# DRV8874_MOTOR_DRV.net
KiCad netlist of a schematic drawn in Altium Designer
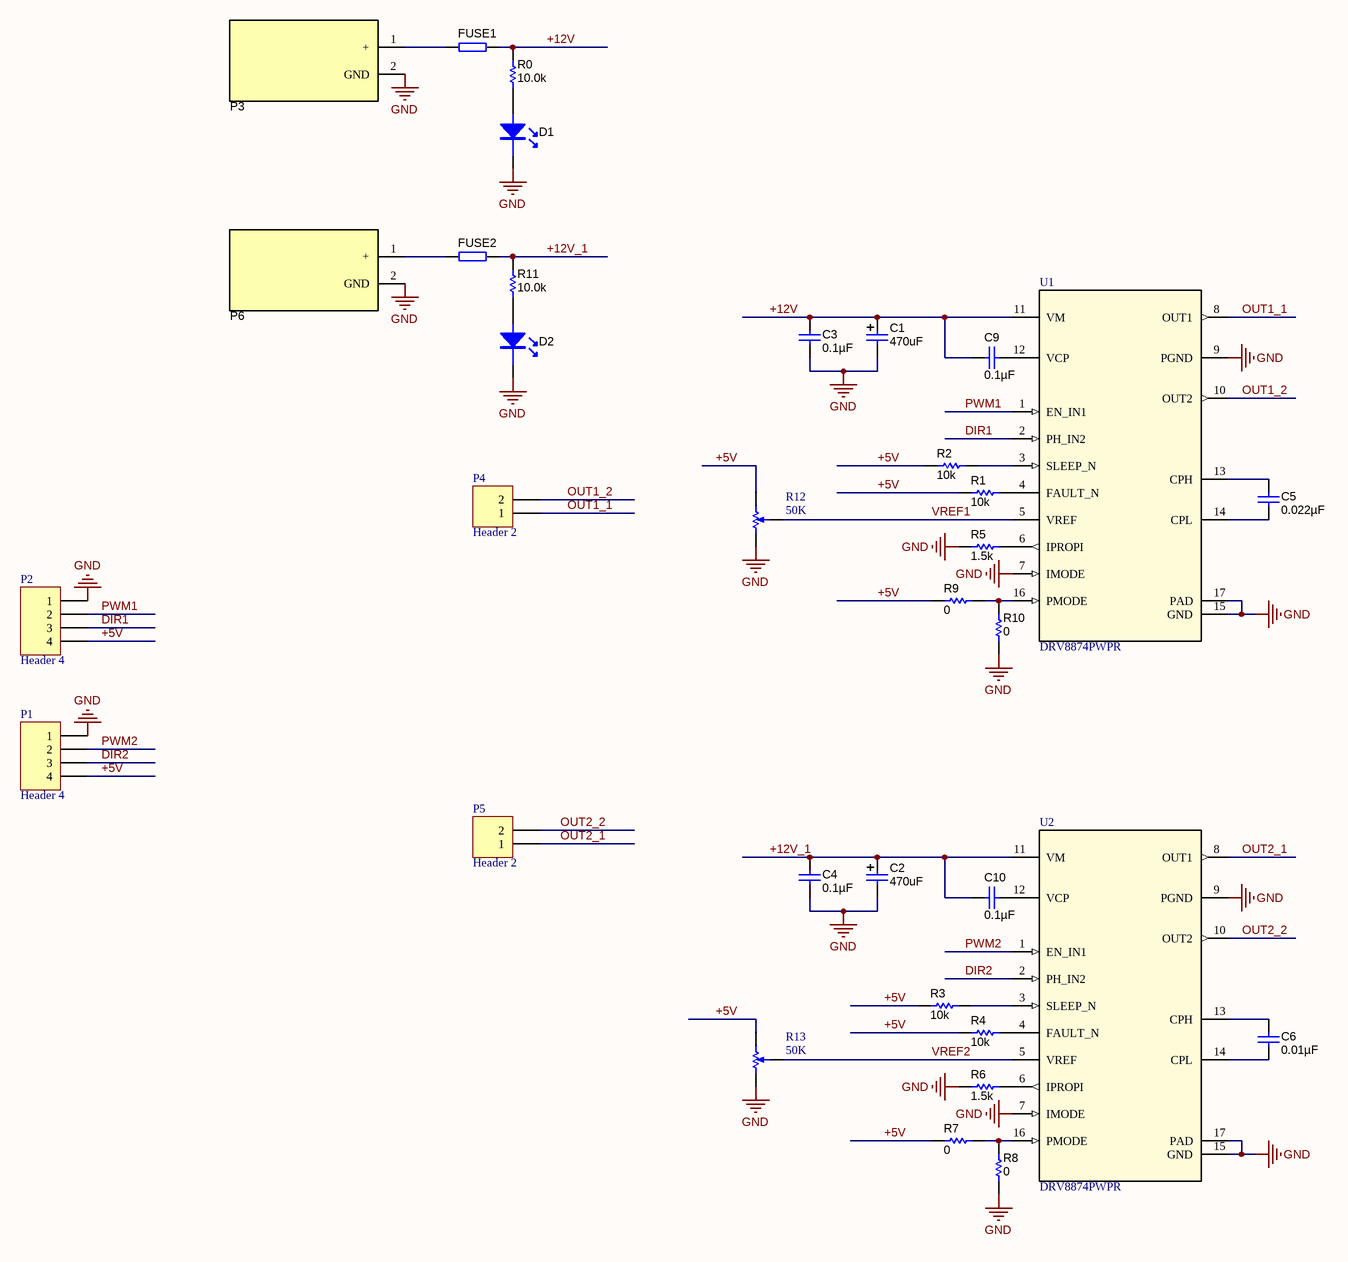
[diagram p0: DRV8874 MOTOR DRV.SchDoc]

(export (version "E")
  (design (tool "Eeschema 10.0.6"))
  (components
    (comp (ref "C1")
      (value "470uF")
      (footprint "CAP")
      (fields (field (name "MANUFACTURER") "Used in BOM report"))
      (libsource (lib "LMD18200 MOTOR DRV") (part "Cap_100uF"))
    )
    (comp (ref "C2")
      (value "470uF")
      (footprint "CAP")
      (fields (field (name "MANUFACTURER") "Used in BOM report"))
      (libsource (lib "LMD18200 MOTOR DRV") (part "Cap_100uF"))
    )
    (comp (ref "C3")
      (value "08051C103JAT2A")
      (footprint "0805_HV")
      (description "CAP, CERM, 0.01 µF, 100 V, +/- 5%, X7R, 0805")
      (fields
        (field (name "VALUEDISPLAYED") "0.1µF")
        (field (name "MANUFACTURER") "AVX")
        (field (name "PUBLISHER") "Texas Instruments")
      )
      (libsource (lib "VFD_CLOCK") (part "08051C103JAT2A"))
    )
    (comp (ref "C4")
      (value "08051C103JAT2A")
      (footprint "0805_HV")
      (description "CAP, CERM, 0.01 µF, 100 V, +/- 5%, X7R, 0805")
      (fields
        (field (name "VALUEDISPLAYED") "0.1µF")
        (field (name "MANUFACTURER") "AVX")
        (field (name "PUBLISHER") "Texas Instruments")
      )
      (libsource (lib "VFD_CLOCK") (part "08051C103JAT2A"))
    )
    (comp (ref "C5")
      (value "08051C103JAT2A")
      (footprint "0805_HV")
      (description "CAP, CERM, 0.01 µF, 100 V, +/- 5%, X7R, 0805")
      (fields
        (field (name "VALUEDISPLAYED") "0.022µF")
        (field (name "MANUFACTURER") "AVX")
        (field (name "PUBLISHER") "Texas Instruments")
      )
      (libsource (lib "VFD_CLOCK") (part "08051C103JAT2A"))
    )
    (comp (ref "C6")
      (value "08051C103JAT2A")
      (footprint "0805_HV")
      (description "CAP, CERM, 0.01 µF, 100 V, +/- 5%, X7R, 0805")
      (fields
        (field (name "VALUEDISPLAYED") "0.01µF")
        (field (name "MANUFACTURER") "AVX")
        (field (name "PUBLISHER") "Texas Instruments")
      )
      (libsource (lib "VFD_CLOCK") (part "08051C103JAT2A"))
    )
    (comp (ref "C9")
      (value "08051C103JAT2A")
      (footprint "0805_HV")
      (description "CAP, CERM, 0.01 µF, 100 V, +/- 5%, X7R, 0805")
      (fields
        (field (name "VALUEDISPLAYED") "0.1µF")
        (field (name "MANUFACTURER") "AVX")
        (field (name "PUBLISHER") "Texas Instruments")
      )
      (libsource (lib "VFD_CLOCK") (part "08051C103JAT2A"))
    )
    (comp (ref "C10")
      (value "08051C103JAT2A")
      (footprint "0805_HV")
      (description "CAP, CERM, 0.01 µF, 100 V, +/- 5%, X7R, 0805")
      (fields
        (field (name "VALUEDISPLAYED") "0.1µF")
        (field (name "MANUFACTURER") "AVX")
        (field (name "PUBLISHER") "Texas Instruments")
      )
      (libsource (lib "VFD_CLOCK") (part "08051C103JAT2A"))
    )
    (comp (ref "D1")
      (value "RED")
      (footprint "0805_HV")
      (description "LED发光管")
      (libsource (lib "Buffer_Board") (part "LED"))
    )
    (comp (ref "D2")
      (value "RED")
      (footprint "0805_HV")
      (description "LED发光管")
      (libsource (lib "Buffer_Board") (part "LED"))
    )
    (comp (ref "FUSE1")
      (value "~")
      (footprint "1206")
      (description "电阻")
      (libsource (lib "Buffer_Board") (part "R"))
    )
    (comp (ref "FUSE2")
      (value "~")
      (footprint "1206")
      (description "电阻")
      (libsource (lib "Buffer_Board") (part "R"))
    )
    (comp (ref "P1")
      (value "Header 4")
      (footprint "HDR1X4")
      (description "Header, 4-Pin")
      (fields (field (name "PUBLISHER") "Altium Limited"))
      (libsource (lib "Miscellaneous Connectors") (part "Header 4"))
    )
    (comp (ref "P2")
      (value "Header 4")
      (footprint "HDR1X4")
      (description "Header, 4-Pin")
      (fields (field (name "PUBLISHER") "Altium Limited"))
      (libsource (lib "Miscellaneous Connectors") (part "Header 4"))
    )
    (comp (ref "P3")
      (value "Used in BOM report")
      (footprint "2p")
      (libsource (lib "VFD_CLOCK") (part "PWR5.5"))
    )
    (comp (ref "P4")
      (value "Header 2")
      (footprint "2p")
      (description "Header, 2-Pin")
      (fields (field (name "PUBLISHER") "Altium Limited"))
      (libsource (lib "Miscellaneous Connectors") (part "Header 2"))
    )
    (comp (ref "P5")
      (value "Header 2")
      (footprint "2p")
      (description "Header, 2-Pin")
      (fields (field (name "PUBLISHER") "Altium Limited"))
      (libsource (lib "Miscellaneous Connectors") (part "Header 2"))
    )
    (comp (ref "P6")
      (value "Used in BOM report")
      (footprint "2p")
      (libsource (lib "VFD_CLOCK") (part "PWR5.5"))
    )
    (comp (ref "R0")
      (value "CRCW080510K0FKEA")
      (footprint "0805_HV")
      (description "RES, 10.0 k, 1%, 0.125 W, 0805")
      (fields
        (field (name "MANUFACTURER") "Vishay-Dale")
        (field (name "VALUEDISPLAYED") "10.0k")
        (field (name "PUBLISHER") "Texas Instruments")
      )
      (libsource (lib "VFD_CLOCK") (part "CRCW080510K0FKEA"))
    )
    (comp (ref "R1")
      (value "CRCW080510K0FKEA")
      (footprint "0805_HV")
      (description "RES, 10.0 k, 1%, 0.125 W, 0805")
      (fields
        (field (name "MANUFACTURER") "Vishay-Dale")
        (field (name "VALUEDISPLAYED") "10k")
        (field (name "PUBLISHER") "Texas Instruments")
      )
      (libsource (lib "VFD_CLOCK") (part "CRCW080510K0FKEA"))
    )
    (comp (ref "R2")
      (value "CRCW080510K0FKEA")
      (footprint "0805_HV")
      (description "RES, 10.0 k, 1%, 0.125 W, 0805")
      (fields
        (field (name "MANUFACTURER") "Vishay-Dale")
        (field (name "VALUEDISPLAYED") "10k")
        (field (name "PUBLISHER") "Texas Instruments")
      )
      (libsource (lib "VFD_CLOCK") (part "CRCW080510K0FKEA"))
    )
    (comp (ref "R3")
      (value "CRCW080510K0FKEA")
      (footprint "0805_HV")
      (description "RES, 10.0 k, 1%, 0.125 W, 0805")
      (fields
        (field (name "MANUFACTURER") "Vishay-Dale")
        (field (name "VALUEDISPLAYED") "10k")
        (field (name "PUBLISHER") "Texas Instruments")
      )
      (libsource (lib "VFD_CLOCK") (part "CRCW080510K0FKEA"))
    )
    (comp (ref "R4")
      (value "CRCW080510K0FKEA")
      (footprint "0805_HV")
      (description "RES, 10.0 k, 1%, 0.125 W, 0805")
      (fields
        (field (name "MANUFACTURER") "Vishay-Dale")
        (field (name "VALUEDISPLAYED") "10k")
        (field (name "PUBLISHER") "Texas Instruments")
      )
      (libsource (lib "VFD_CLOCK") (part "CRCW080510K0FKEA"))
    )
    (comp (ref "R5")
      (value "CRCW080510K0FKEA")
      (footprint "0805_HV")
      (description "RES, 10.0 k, 1%, 0.125 W, 0805")
      (fields
        (field (name "MANUFACTURER") "Vishay-Dale")
        (field (name "VALUEDISPLAYED") "1.5k")
        (field (name "PUBLISHER") "Texas Instruments")
      )
      (libsource (lib "VFD_CLOCK") (part "CRCW080510K0FKEA"))
    )
    (comp (ref "R6")
      (value "CRCW080510K0FKEA")
      (footprint "0805_HV")
      (description "RES, 10.0 k, 1%, 0.125 W, 0805")
      (fields
        (field (name "MANUFACTURER") "Vishay-Dale")
        (field (name "VALUEDISPLAYED") "1.5k")
        (field (name "PUBLISHER") "Texas Instruments")
      )
      (libsource (lib "VFD_CLOCK") (part "CRCW080510K0FKEA"))
    )
    (comp (ref "R7")
      (value "CRCW080510K0FKEA")
      (footprint "0805_HV")
      (description "RES, 10.0 k, 1%, 0.125 W, 0805")
      (fields
        (field (name "MANUFACTURER") "Vishay-Dale")
        (field (name "VALUEDISPLAYED") "0")
        (field (name "PUBLISHER") "Texas Instruments")
      )
      (libsource (lib "VFD_CLOCK") (part "CRCW080510K0FKEA"))
    )
    (comp (ref "R8")
      (value "CRCW080510K0FKEA")
      (footprint "0805_HV")
      (description "RES, 10.0 k, 1%, 0.125 W, 0805")
      (fields
        (field (name "MANUFACTURER") "Vishay-Dale")
        (field (name "VALUEDISPLAYED") "0")
        (field (name "PUBLISHER") "Texas Instruments")
      )
      (libsource (lib "VFD_CLOCK") (part "CRCW080510K0FKEA"))
    )
    (comp (ref "R9")
      (value "CRCW080510K0FKEA")
      (footprint "0805_HV")
      (description "RES, 10.0 k, 1%, 0.125 W, 0805")
      (fields
        (field (name "MANUFACTURER") "Vishay-Dale")
        (field (name "VALUEDISPLAYED") "0")
        (field (name "PUBLISHER") "Texas Instruments")
      )
      (libsource (lib "VFD_CLOCK") (part "CRCW080510K0FKEA"))
    )
    (comp (ref "R10")
      (value "CRCW080510K0FKEA")
      (footprint "0805_HV")
      (description "RES, 10.0 k, 1%, 0.125 W, 0805")
      (fields
        (field (name "MANUFACTURER") "Vishay-Dale")
        (field (name "VALUEDISPLAYED") "0")
        (field (name "PUBLISHER") "Texas Instruments")
      )
      (libsource (lib "VFD_CLOCK") (part "CRCW080510K0FKEA"))
    )
    (comp (ref "R11")
      (value "CRCW080510K0FKEA")
      (footprint "0805_HV")
      (description "RES, 10.0 k, 1%, 0.125 W, 0805")
      (fields
        (field (name "MANUFACTURER") "Vishay-Dale")
        (field (name "VALUEDISPLAYED") "10.0k")
        (field (name "PUBLISHER") "Texas Instruments")
      )
      (libsource (lib "VFD_CLOCK") (part "CRCW080510K0FKEA"))
    )
    (comp (ref "R12")
      (value "50K")
      (footprint "POT4MM-2")
      (description "Square Trimming Potentiometer")
      (fields (field (name "PUBLISHER") "Altium Limited"))
      (libsource (lib "Miscellaneous Devices") (part "RPot SM"))
    )
    (comp (ref "R13")
      (value "50K")
      (footprint "POT4MM-2")
      (description "Square Trimming Potentiometer")
      (fields (field (name "PUBLISHER") "Altium Limited"))
      (libsource (lib "Miscellaneous Devices") (part "RPot SM"))
    )
    (comp (ref "U1")
      (value "DRV8874PWPR")
      (footprint "PWP0016J_M")
      (description "Imported")
      (fields (field (name "MANUFACTURER") "Texas Instruments"))
      (libsource (lib "2019-07-25_10-04-02") (part "DRV8874PWPR"))
    )
    (comp (ref "U2")
      (value "DRV8874PWPR")
      (footprint "PWP0016J_M")
      (description "Imported")
      (fields (field (name "MANUFACTURER") "Texas Instruments"))
      (libsource (lib "2019-07-25_10-04-02") (part "DRV8874PWPR"))
    )
  )
  (nets
    (net (code "1") (name "/+5V") (class "Default")
      (node (ref "P1") (pin "4") (pinfunction "4_4") (pintype "passive"))
      (node (ref "P2") (pin "4") (pinfunction "4_4") (pintype "passive"))
      (node (ref "R1") (pin "2") (pinfunction "2_2") (pintype "passive"))
      (node (ref "R12") (pin "CW") (pinfunction "+_CW") (pintype "passive"))
      (node (ref "R13") (pin "CW") (pinfunction "+_CW") (pintype "passive"))
      (node (ref "R2") (pin "2") (pinfunction "2_2") (pintype "passive"))
      (node (ref "R3") (pin "2") (pinfunction "2_2") (pintype "passive"))
      (node (ref "R4") (pin "2") (pinfunction "2_2") (pintype "passive"))
      (node (ref "R7") (pin "2") (pinfunction "2_2") (pintype "passive"))
      (node (ref "R9") (pin "1") (pinfunction "1_1") (pintype "passive"))
    )
    (net (code "2") (name "/+12V") (class "Default")
      (node (ref "C1") (pin "2") (pinfunction "2_2") (pintype "passive"))
      (node (ref "C3") (pin "1") (pinfunction "1_1") (pintype "passive"))
      (node (ref "C9") (pin "1") (pinfunction "1_1") (pintype "passive"))
      (node (ref "FUSE1") (pin "2") (pinfunction "2_2") (pintype "passive"))
      (node (ref "R0") (pin "1") (pinfunction "1_1") (pintype "passive"))
      (node (ref "U1") (pin "11") (pinfunction "VM_11") (pintype "power_in"))
    )
    (net (code "3") (name "/+12V_1") (class "Default")
      (node (ref "C10") (pin "1") (pinfunction "1_1") (pintype "passive"))
      (node (ref "C2") (pin "2") (pinfunction "2_2") (pintype "passive"))
      (node (ref "C4") (pin "1") (pinfunction "1_1") (pintype "passive"))
      (node (ref "FUSE2") (pin "2") (pinfunction "2_2") (pintype "passive"))
      (node (ref "R11") (pin "1") (pinfunction "1_1") (pintype "passive"))
      (node (ref "U2") (pin "11") (pinfunction "VM_11") (pintype "power_in"))
    )
    (net (code "4") (name "/DIR1") (class "Default")
      (node (ref "P2") (pin "3") (pinfunction "3_3") (pintype "passive"))
      (node (ref "U1") (pin "2") (pinfunction "PH_IN2_2") (pintype "input"))
    )
    (net (code "5") (name "/DIR2") (class "Default")
      (node (ref "P1") (pin "3") (pinfunction "3_3") (pintype "passive"))
      (node (ref "U2") (pin "2") (pinfunction "PH_IN2_2") (pintype "input"))
    )
    (net (code "6") (name "/OUT1_1") (class "Default")
      (node (ref "P4") (pin "1") (pinfunction "1_1") (pintype "passive"))
      (node (ref "U1") (pin "8") (pinfunction "OUT1_8") (pintype "output"))
    )
    (net (code "7") (name "/OUT1_2") (class "Default")
      (node (ref "P4") (pin "2") (pinfunction "2_2") (pintype "passive"))
      (node (ref "U1") (pin "10") (pinfunction "OUT2_10") (pintype "output"))
    )
    (net (code "8") (name "/OUT2_1") (class "Default")
      (node (ref "P5") (pin "1") (pinfunction "1_1") (pintype "passive"))
      (node (ref "U2") (pin "8") (pinfunction "OUT1_8") (pintype "output"))
    )
    (net (code "9") (name "/OUT2_2") (class "Default")
      (node (ref "P5") (pin "2") (pinfunction "2_2") (pintype "passive"))
      (node (ref "U2") (pin "10") (pinfunction "OUT2_10") (pintype "output"))
    )
    (net (code "10") (name "/PWM1") (class "Default")
      (node (ref "P2") (pin "2") (pinfunction "2_2") (pintype "passive"))
      (node (ref "U1") (pin "1") (pinfunction "EN_IN1_1") (pintype "input"))
    )
    (net (code "11") (name "/PWM2") (class "Default")
      (node (ref "P1") (pin "2") (pinfunction "2_2") (pintype "passive"))
      (node (ref "U2") (pin "1") (pinfunction "EN_IN1_1") (pintype "input"))
    )
    (net (code "12") (name "/VREF1") (class "Default")
      (node (ref "R12") (pin "W") (pinfunction "W_W") (pintype "passive"))
      (node (ref "U1") (pin "5") (pinfunction "VREF_5") (pintype "power_in"))
    )
    (net (code "13") (name "/VREF2") (class "Default")
      (node (ref "R13") (pin "W") (pinfunction "W_W") (pintype "passive"))
      (node (ref "U2") (pin "5") (pinfunction "VREF_5") (pintype "power_in"))
    )
    (net (code "14") (name "GND") (class "Default")
      (node (ref "C1") (pin "1") (pinfunction "1_1") (pintype "passive"))
      (node (ref "C2") (pin "1") (pinfunction "1_1") (pintype "passive"))
      (node (ref "C3") (pin "2") (pinfunction "2_2") (pintype "passive"))
      (node (ref "C4") (pin "2") (pinfunction "2_2") (pintype "passive"))
      (node (ref "D1") (pin "2") (pinfunction "2_2") (pintype "passive"))
      (node (ref "D2") (pin "2") (pinfunction "2_2") (pintype "passive"))
      (node (ref "P1") (pin "1") (pinfunction "1_1") (pintype "passive"))
      (node (ref "P2") (pin "1") (pinfunction "1_1") (pintype "passive"))
      (node (ref "P3") (pin "2") (pinfunction "GND_2") (pintype "passive"))
      (node (ref "P6") (pin "2") (pinfunction "GND_2") (pintype "passive"))
      (node (ref "R10") (pin "2") (pinfunction "2_2") (pintype "passive"))
      (node (ref "R12") (pin "CCW") (pinfunction "-_CCW") (pintype "passive"))
      (node (ref "R13") (pin "CCW") (pinfunction "-_CCW") (pintype "passive"))
      (node (ref "R5") (pin "2") (pinfunction "2_2") (pintype "passive"))
      (node (ref "R6") (pin "2") (pinfunction "2_2") (pintype "passive"))
      (node (ref "R8") (pin "2") (pinfunction "2_2") (pintype "passive"))
      (node (ref "U1") (pin "15") (pinfunction "GND_15") (pintype "power_in"))
      (node (ref "U1") (pin "17") (pinfunction "PAD_17") (pintype "power_in"))
      (node (ref "U1") (pin "7") (pinfunction "IMODE_7") (pintype "input"))
      (node (ref "U1") (pin "9") (pinfunction "PGND_9") (pintype "power_in"))
      (node (ref "U2") (pin "15") (pinfunction "GND_15") (pintype "power_in"))
      (node (ref "U2") (pin "17") (pinfunction "PAD_17") (pintype "power_in"))
      (node (ref "U2") (pin "7") (pinfunction "IMODE_7") (pintype "input"))
      (node (ref "U2") (pin "9") (pinfunction "PGND_9") (pintype "power_in"))
    )
    (net (code "15") (name "Net-(D1-Pad1)") (class "Default")
      (node (ref "D1") (pin "1") (pinfunction "1_1") (pintype "passive"))
      (node (ref "R0") (pin "2") (pinfunction "2_2") (pintype "passive"))
    )
    (net (code "16") (name "Net-(D2-Pad1)") (class "Default")
      (node (ref "D2") (pin "1") (pinfunction "1_1") (pintype "passive"))
      (node (ref "R11") (pin "2") (pinfunction "2_2") (pintype "passive"))
    )
    (net (code "17") (name "Net-(P3-+)") (class "Default")
      (node (ref "FUSE1") (pin "1") (pinfunction "1_1") (pintype "passive"))
      (node (ref "P3") (pin "1") (pinfunction "+_1") (pintype "passive"))
    )
    (net (code "18") (name "Net-(P6-+)") (class "Default")
      (node (ref "FUSE2") (pin "1") (pinfunction "1_1") (pintype "passive"))
      (node (ref "P6") (pin "1") (pinfunction "+_1") (pintype "passive"))
    )
    (net (code "19") (name "Net-(U1-CPH)") (class "Default")
      (node (ref "C5") (pin "2") (pinfunction "2_2") (pintype "passive"))
      (node (ref "U1") (pin "13") (pinfunction "CPH_13") (pintype "power_in"))
    )
    (net (code "20") (name "Net-(U1-CPL)") (class "Default")
      (node (ref "C5") (pin "1") (pinfunction "1_1") (pintype "passive"))
      (node (ref "U1") (pin "14") (pinfunction "CPL_14") (pintype "power_in"))
    )
    (net (code "21") (name "Net-(U1-FAULT_N)") (class "Default")
      (node (ref "R1") (pin "1") (pinfunction "1_1") (pintype "passive"))
      (node (ref "U1") (pin "4") (pinfunction "FAULT_N_4") (pintype "open_collector"))
    )
    (net (code "22") (name "Net-(U1-IPROPI)") (class "Default")
      (node (ref "R5") (pin "1") (pinfunction "1_1") (pintype "passive"))
      (node (ref "U1") (pin "6") (pinfunction "IPROPI_6") (pintype "output"))
    )
    (net (code "23") (name "Net-(U1-PMODE)") (class "Default")
      (node (ref "R10") (pin "1") (pinfunction "1_1") (pintype "passive"))
      (node (ref "R9") (pin "2") (pinfunction "2_2") (pintype "passive"))
      (node (ref "U1") (pin "16") (pinfunction "PMODE_16") (pintype "input"))
    )
    (net (code "24") (name "Net-(U1-SLEEP_N)") (class "Default")
      (node (ref "R2") (pin "1") (pinfunction "1_1") (pintype "passive"))
      (node (ref "U1") (pin "3") (pinfunction "SLEEP_N_3") (pintype "input"))
    )
    (net (code "25") (name "Net-(U1-VCP)") (class "Default")
      (node (ref "C9") (pin "2") (pinfunction "2_2") (pintype "passive"))
      (node (ref "U1") (pin "12") (pinfunction "VCP_12") (pintype "power_in"))
    )
    (net (code "26") (name "Net-(U2-CPH)") (class "Default")
      (node (ref "C6") (pin "2") (pinfunction "2_2") (pintype "passive"))
      (node (ref "U2") (pin "13") (pinfunction "CPH_13") (pintype "power_in"))
    )
    (net (code "27") (name "Net-(U2-CPL)") (class "Default")
      (node (ref "C6") (pin "1") (pinfunction "1_1") (pintype "passive"))
      (node (ref "U2") (pin "14") (pinfunction "CPL_14") (pintype "power_in"))
    )
    (net (code "28") (name "Net-(U2-FAULT_N)") (class "Default")
      (node (ref "R4") (pin "1") (pinfunction "1_1") (pintype "passive"))
      (node (ref "U2") (pin "4") (pinfunction "FAULT_N_4") (pintype "open_collector"))
    )
    (net (code "29") (name "Net-(U2-IPROPI)") (class "Default")
      (node (ref "R6") (pin "1") (pinfunction "1_1") (pintype "passive"))
      (node (ref "U2") (pin "6") (pinfunction "IPROPI_6") (pintype "output"))
    )
    (net (code "30") (name "Net-(U2-PMODE)") (class "Default")
      (node (ref "R7") (pin "1") (pinfunction "1_1") (pintype "passive"))
      (node (ref "R8") (pin "1") (pinfunction "1_1") (pintype "passive"))
      (node (ref "U2") (pin "16") (pinfunction "PMODE_16") (pintype "input"))
    )
    (net (code "31") (name "Net-(U2-SLEEP_N)") (class "Default")
      (node (ref "R3") (pin "1") (pinfunction "1_1") (pintype "passive"))
      (node (ref "U2") (pin "3") (pinfunction "SLEEP_N_3") (pintype "input"))
    )
    (net (code "32") (name "Net-(U2-VCP)") (class "Default")
      (node (ref "C10") (pin "2") (pinfunction "2_2") (pintype "passive"))
      (node (ref "U2") (pin "12") (pinfunction "VCP_12") (pintype "power_in"))
    )
  )
)
